# baxandall.net
KiCad netlist of a schematic drawn in EAGLE
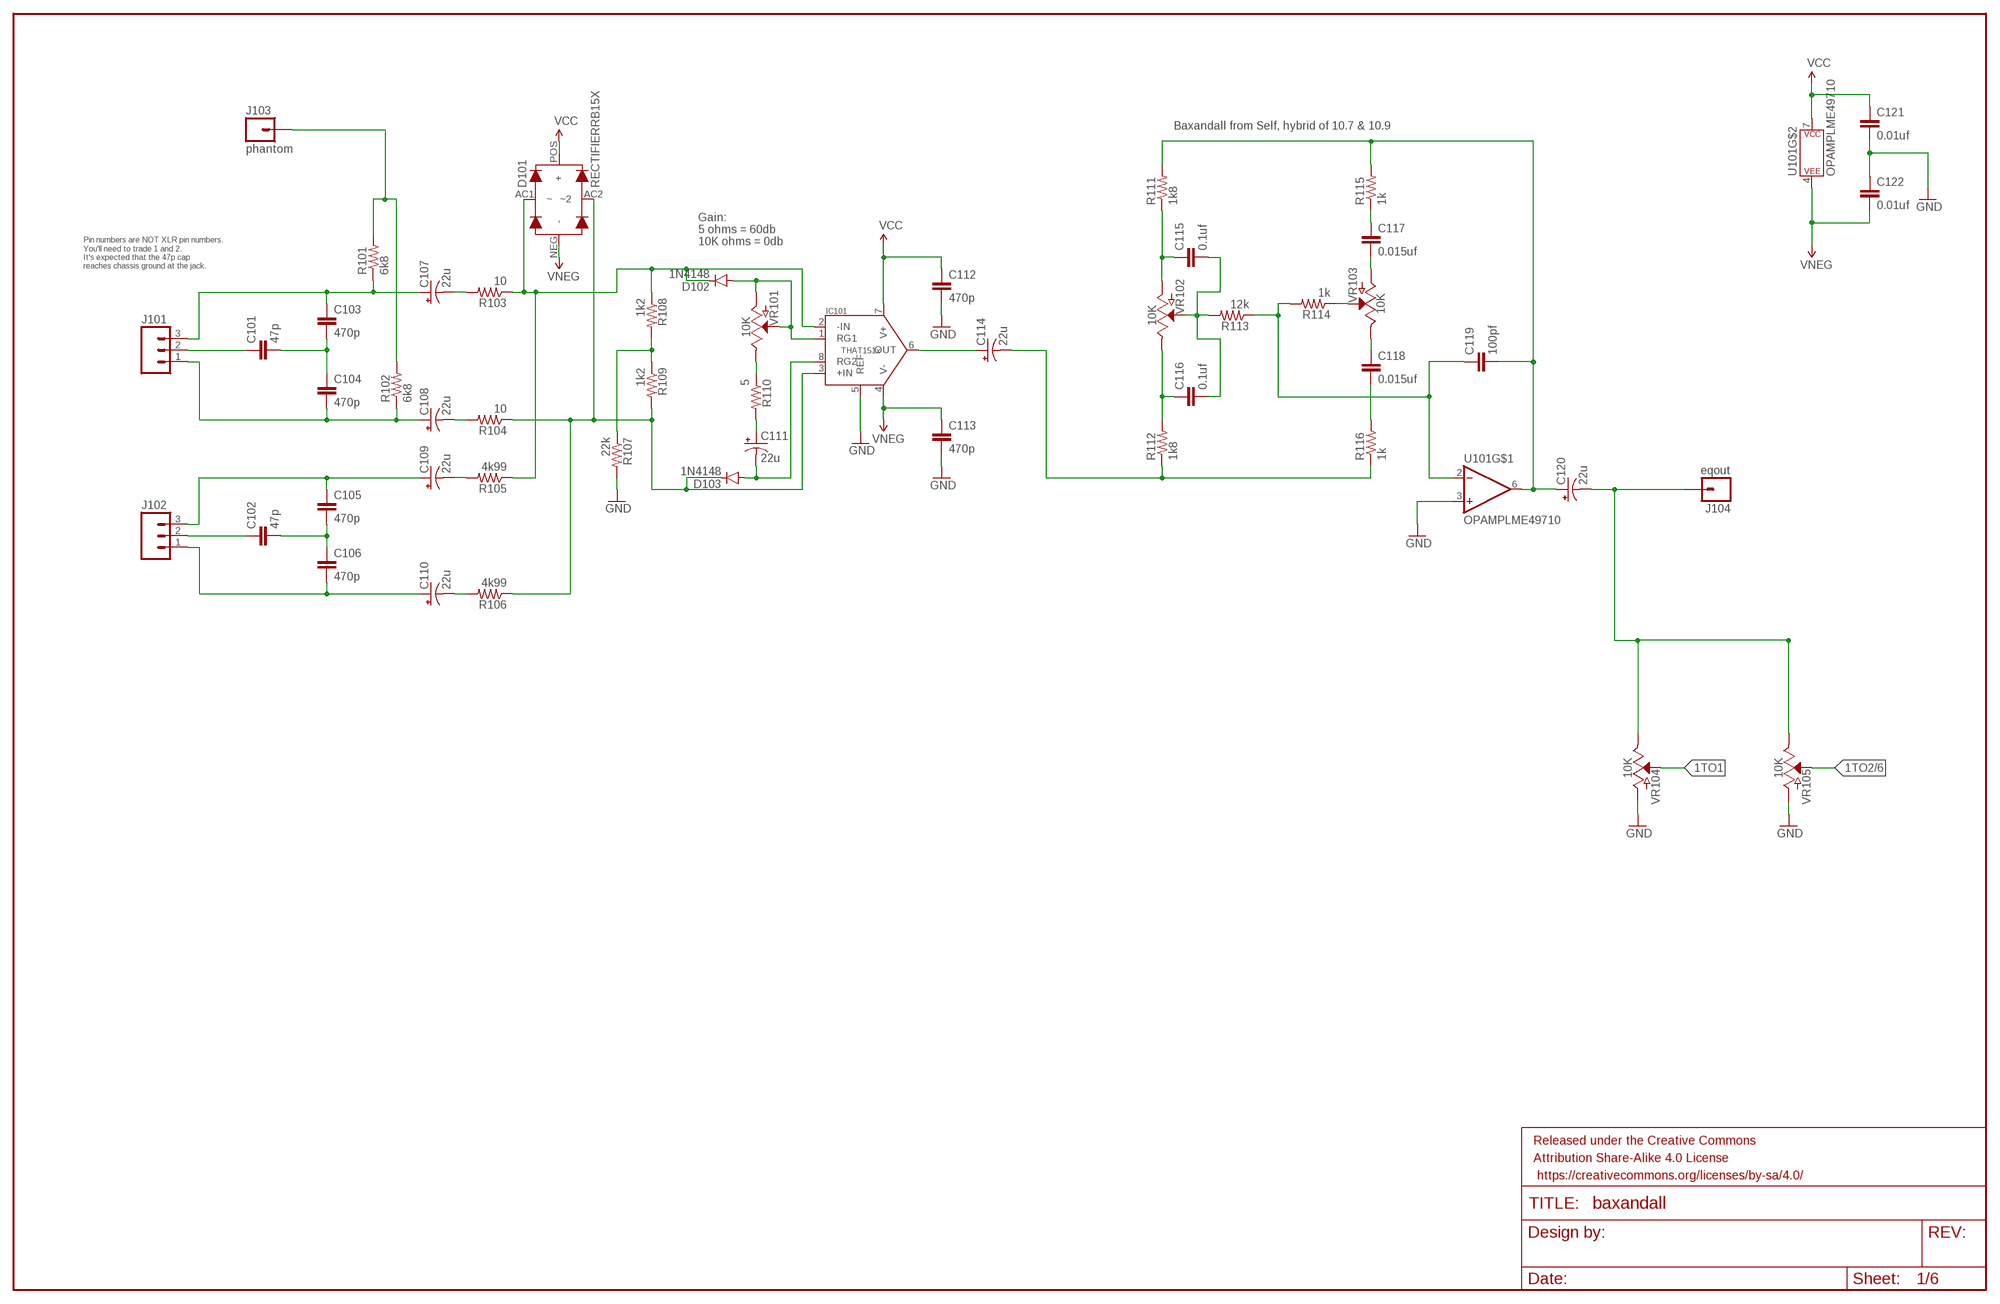
[diagram p0: schematic, sheet 1]
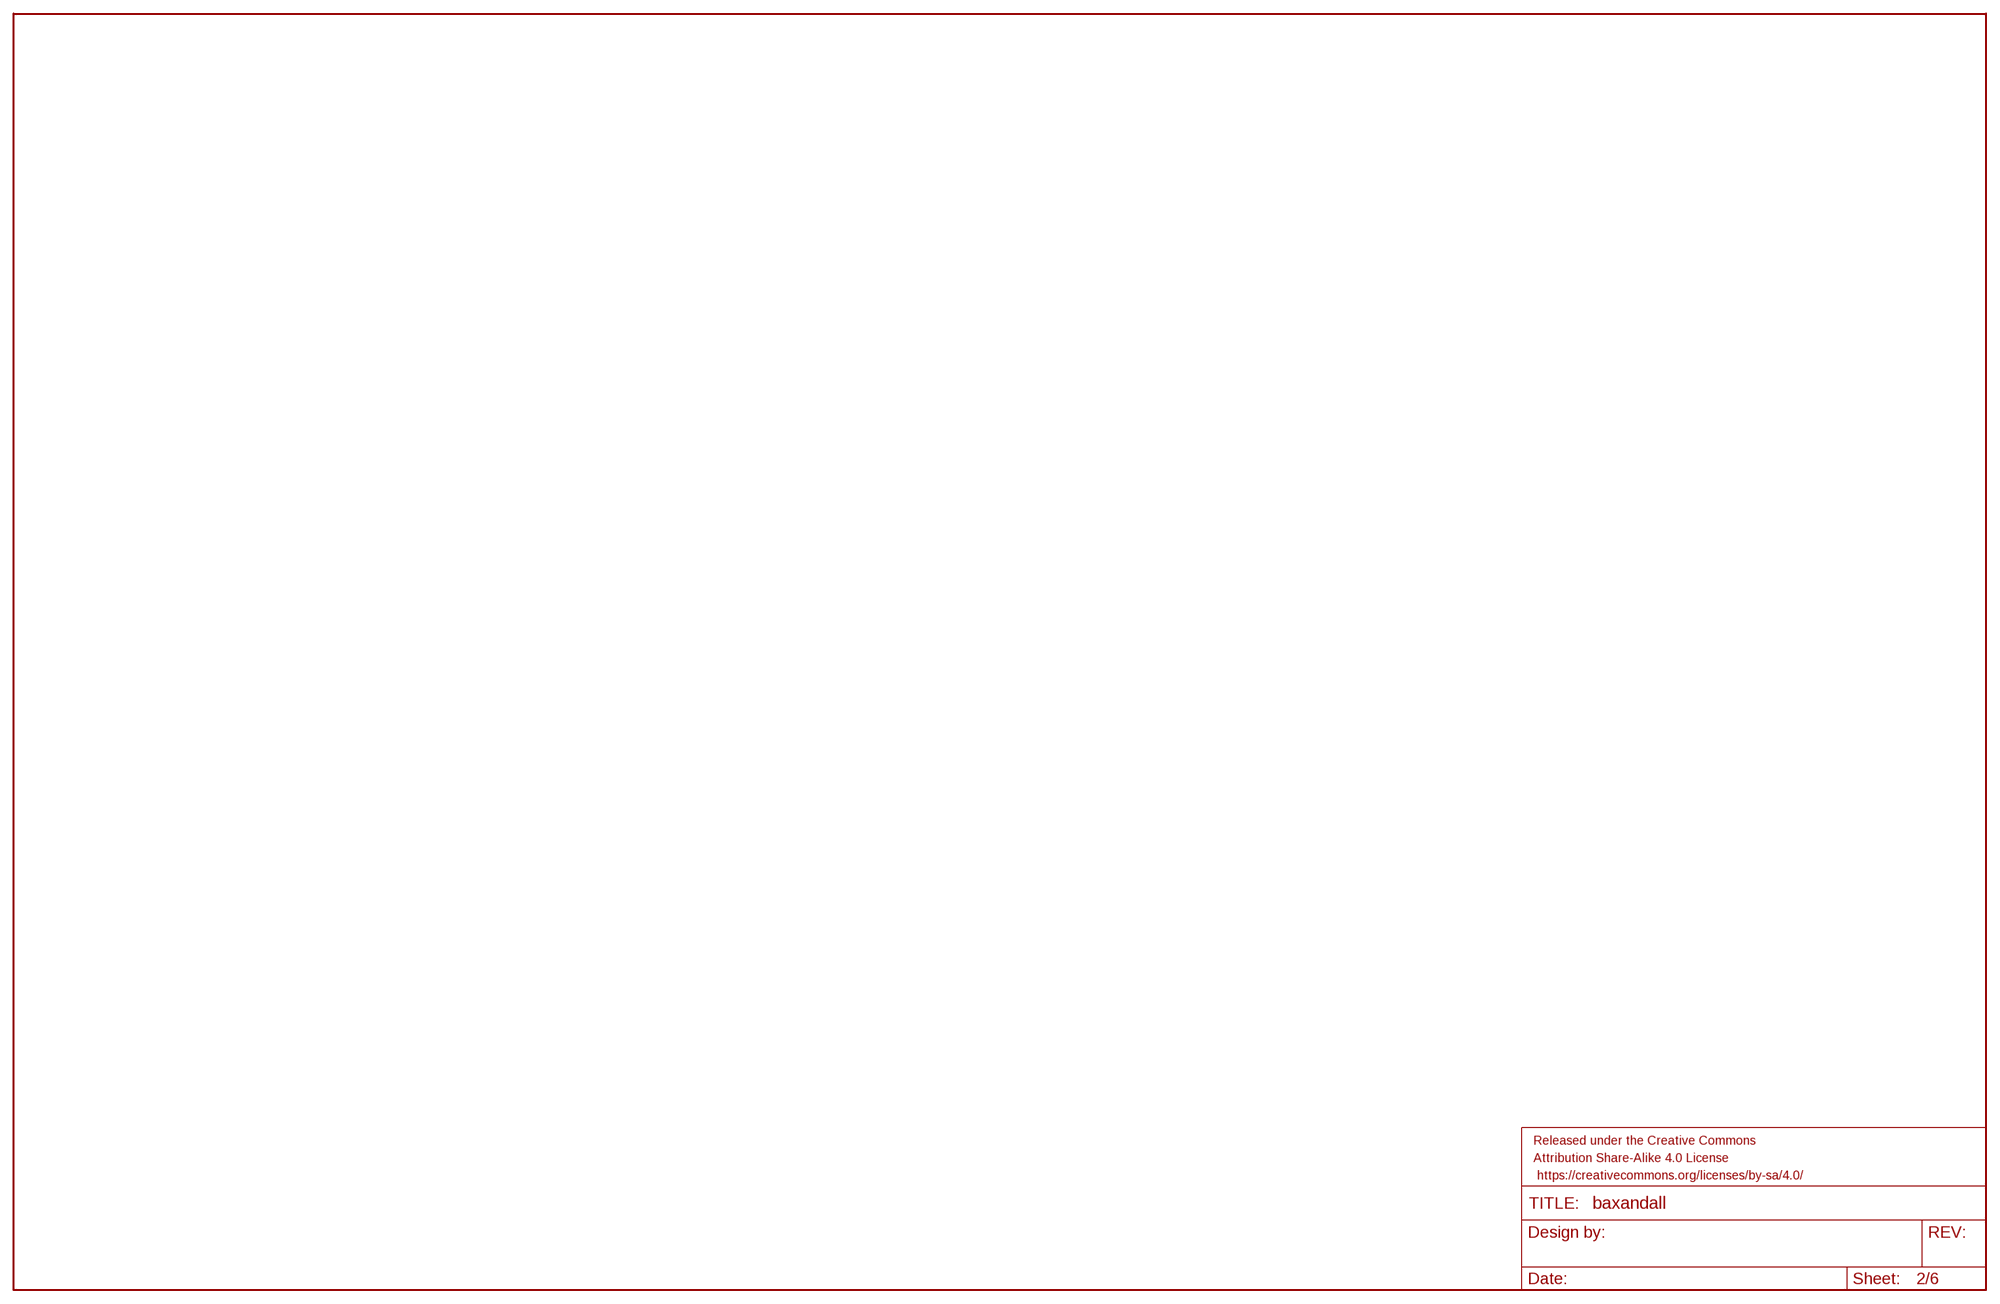
[diagram p1: schematic, sheet 2]
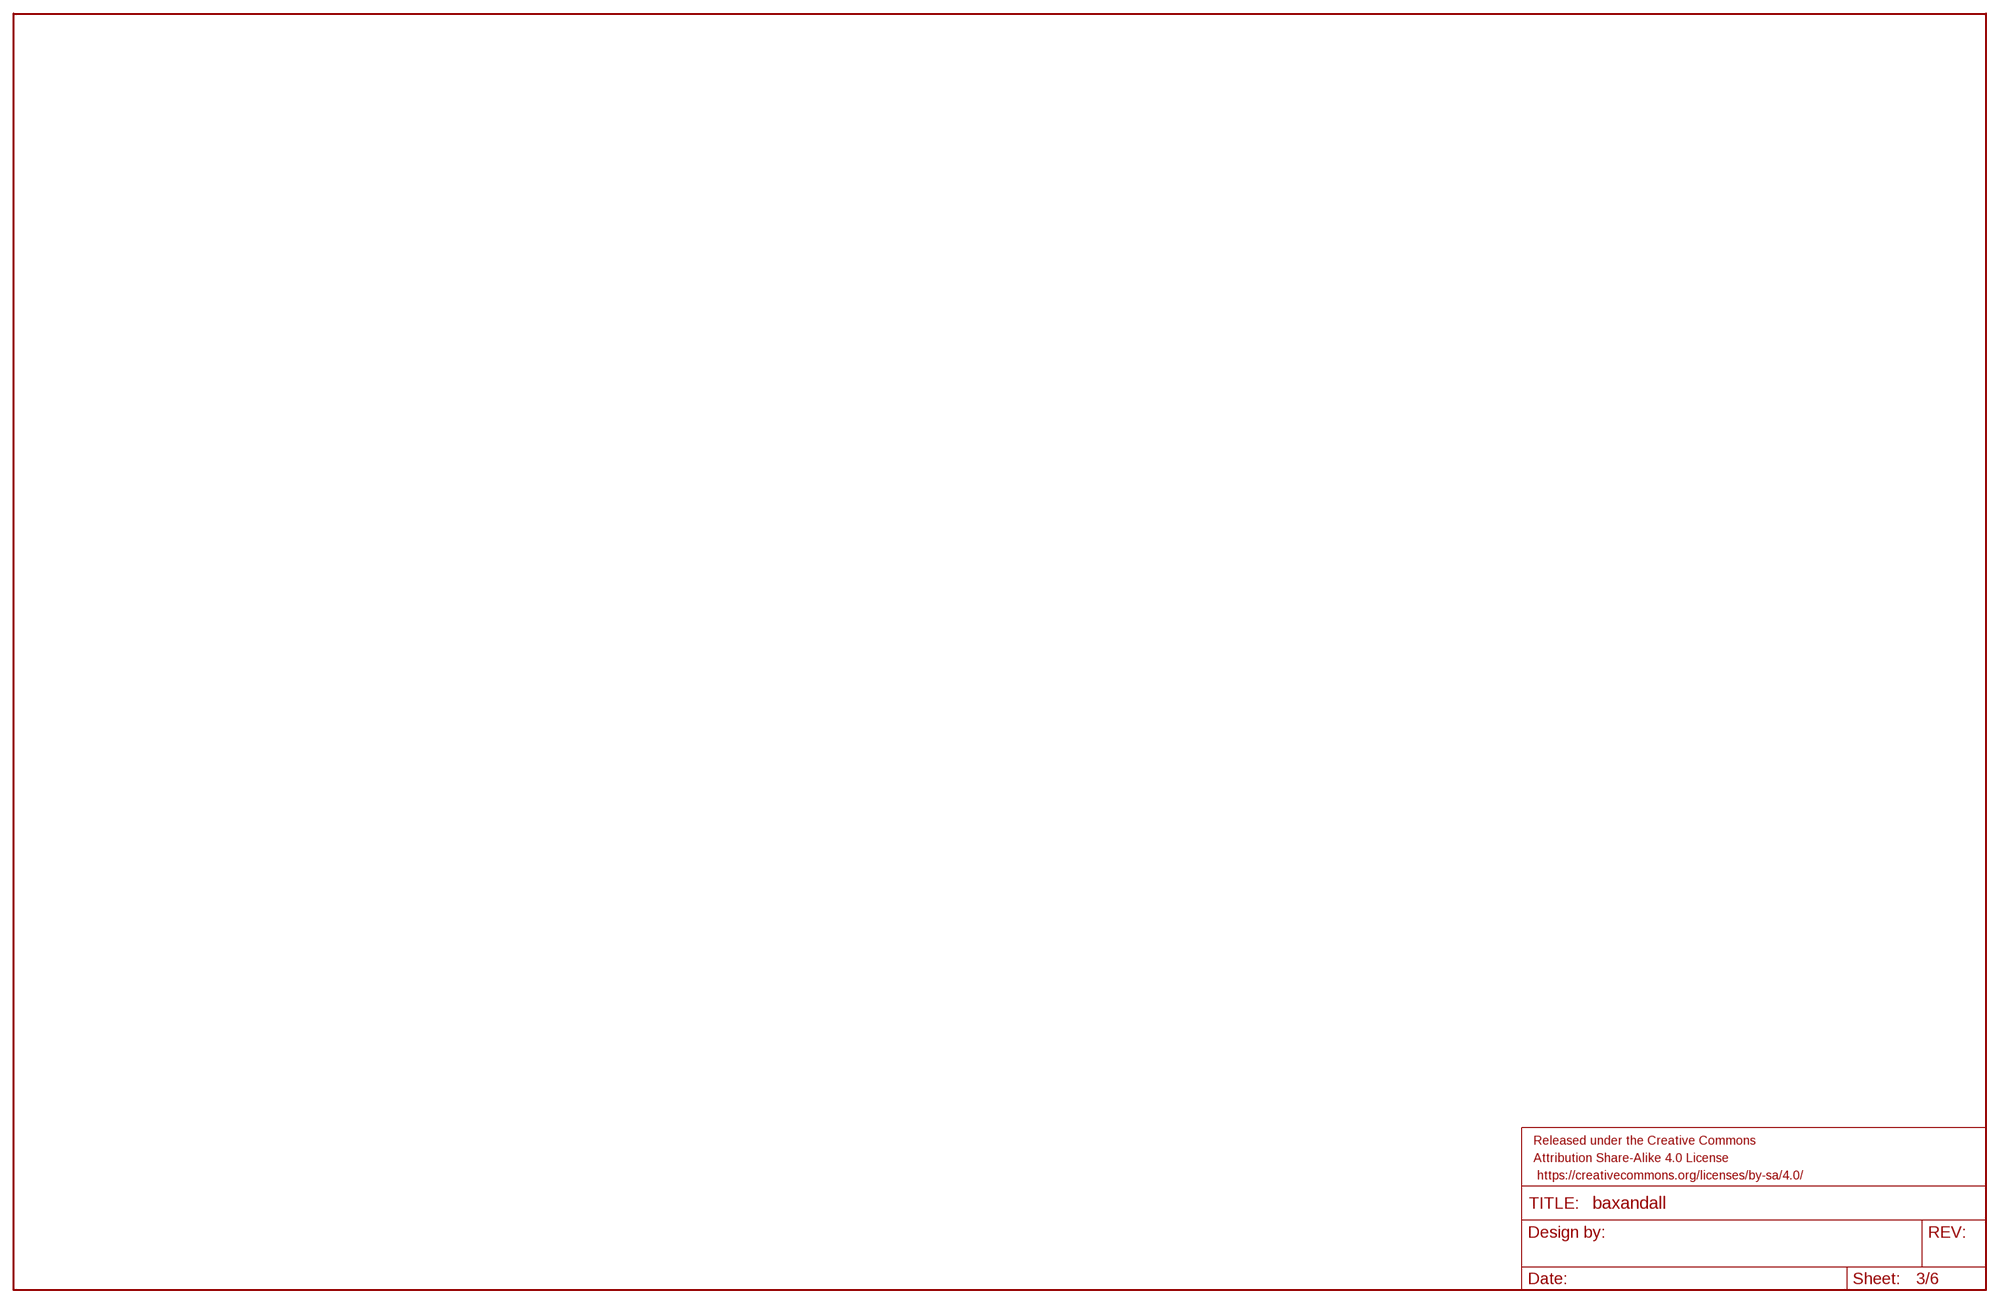
[diagram p2: schematic, sheet 3]
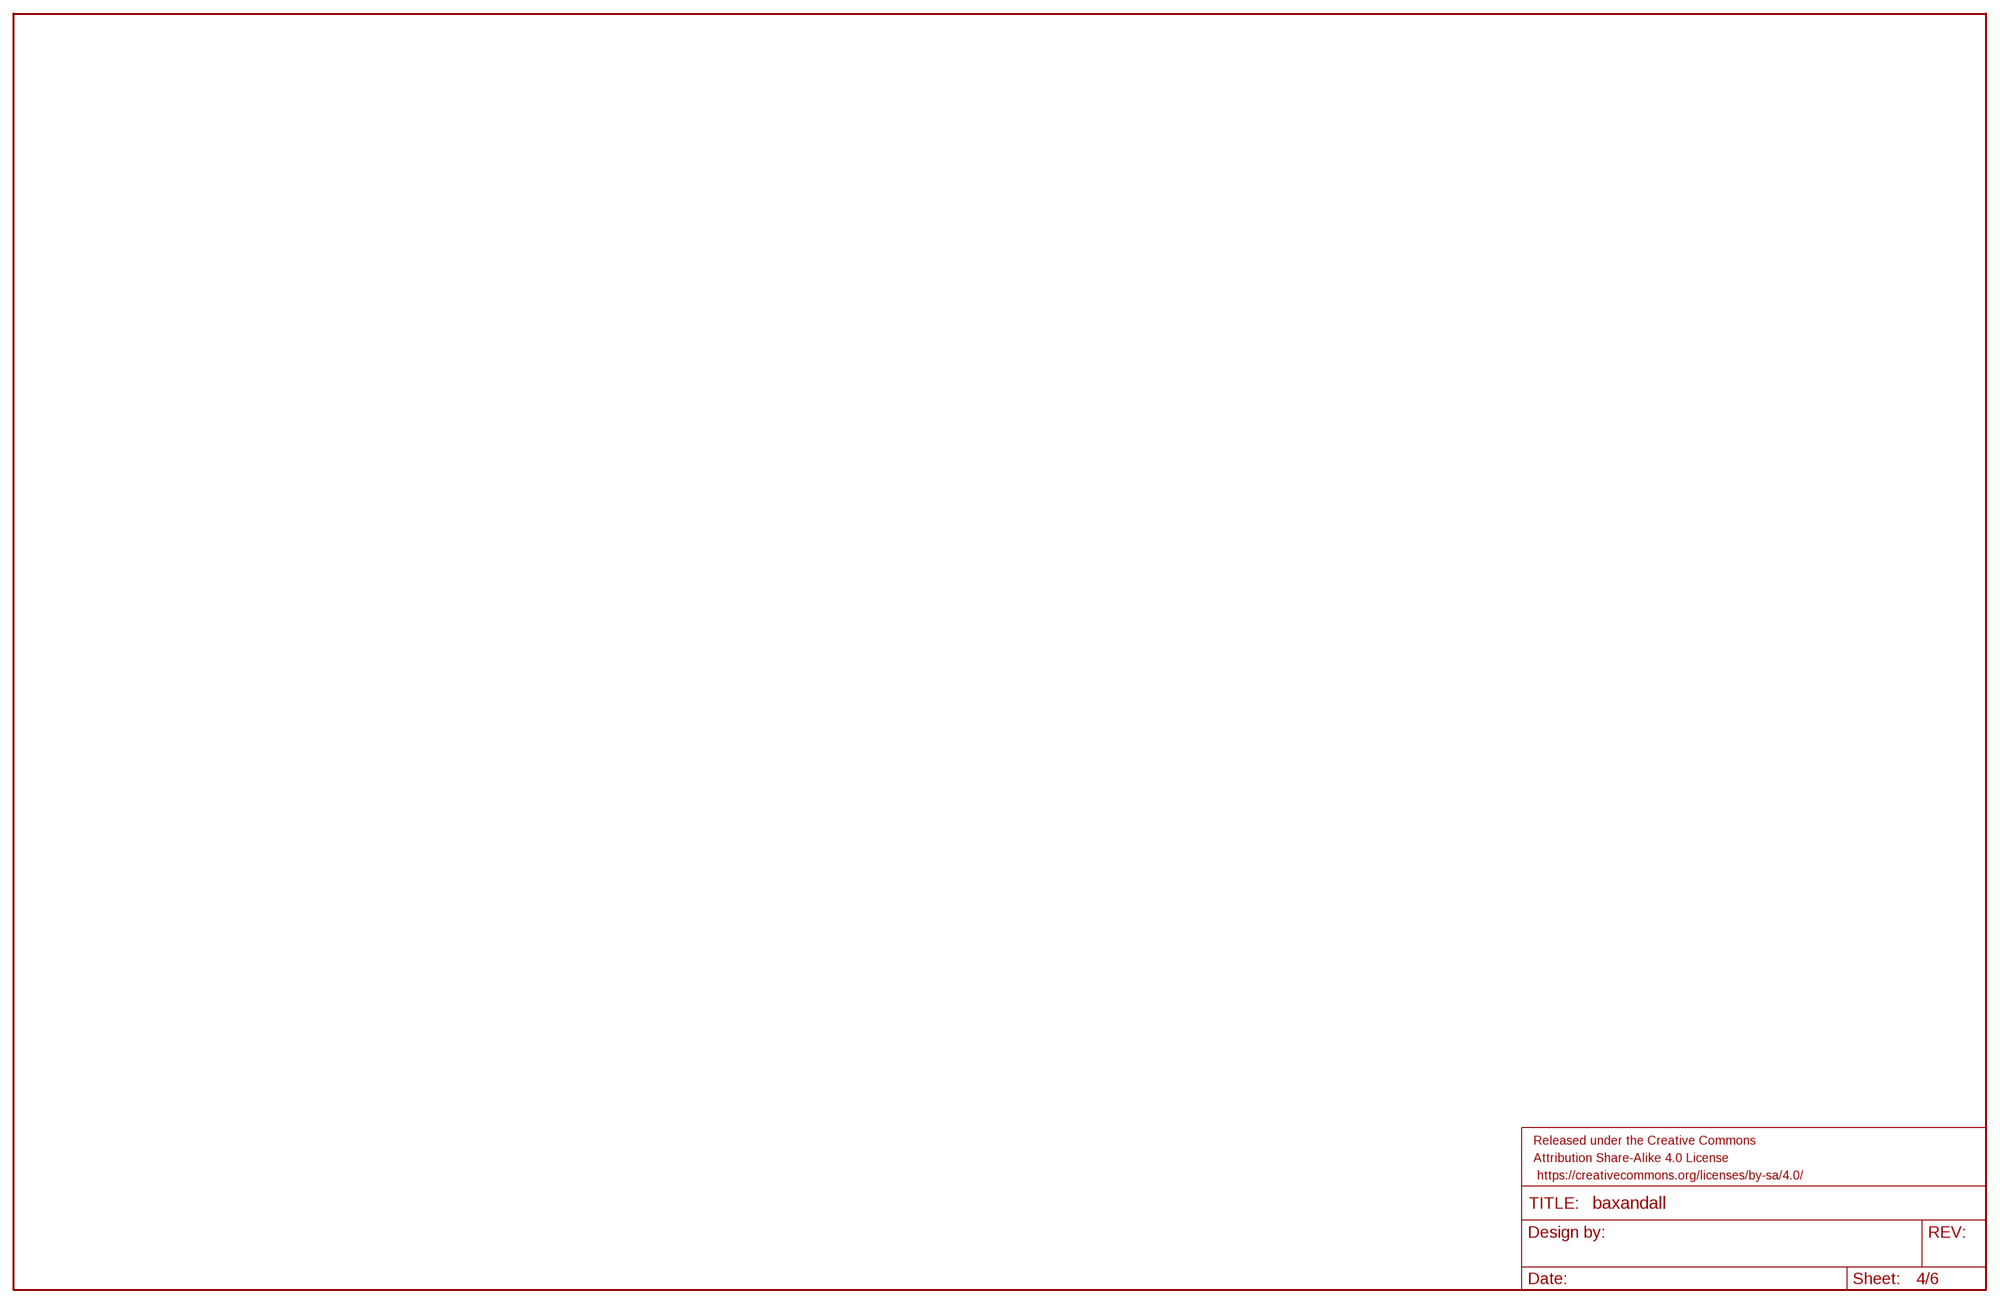
[diagram p3: schematic, sheet 4]
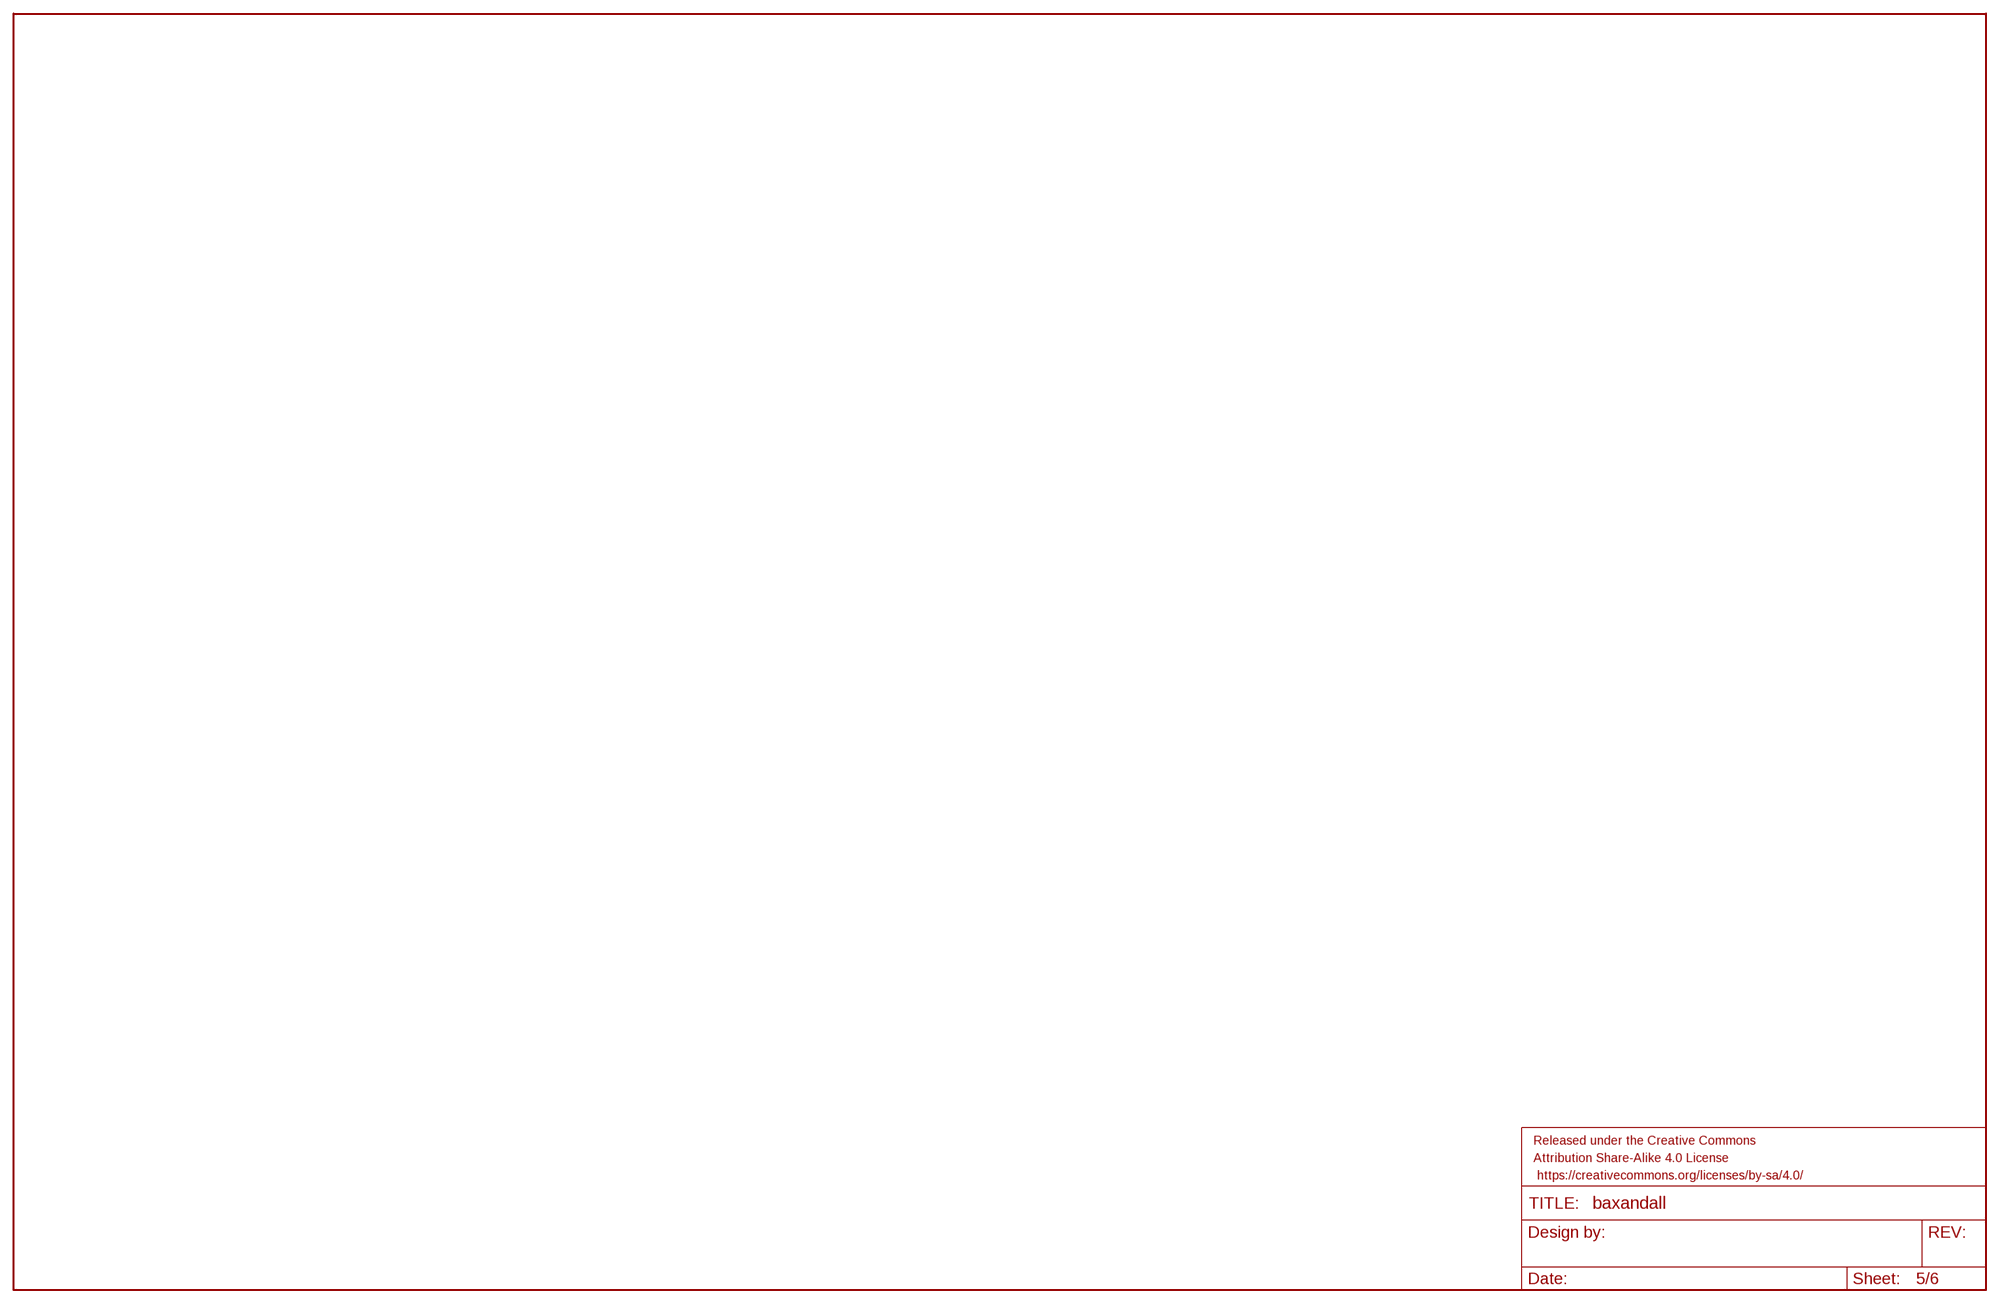
[diagram p4: schematic, sheet 5]
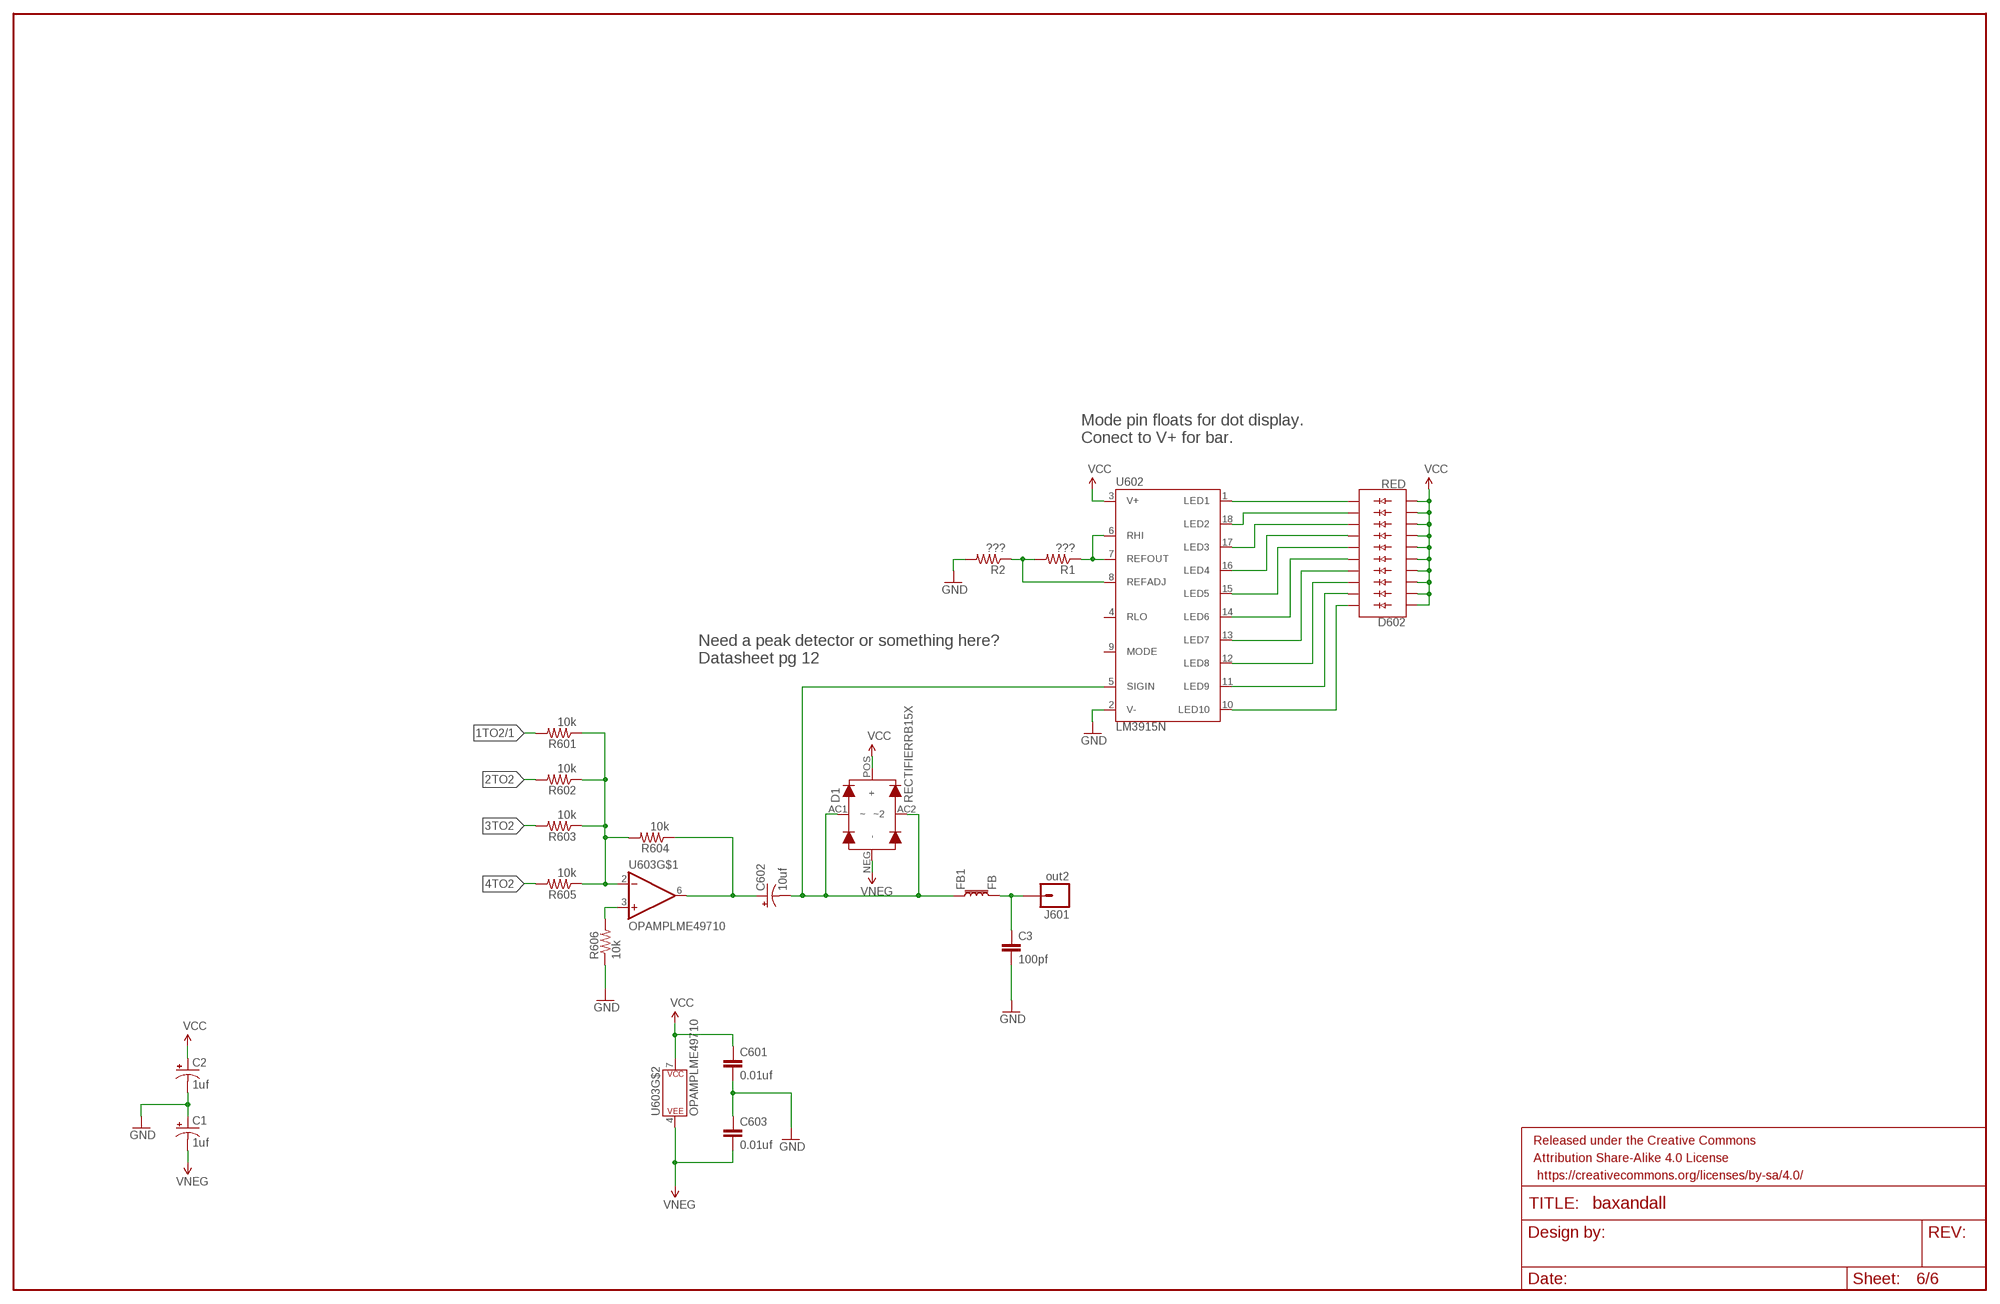
[diagram p5: schematic, sheet 6]

(export (version "E")
  (design (tool "Eeschema 10.0.6"))
  (components
    (comp (ref "FRAME401")
      (value "FRAME-LEDGER")
      (footprint "eagle-import:CREATIVE_COMMONS")
      (libsource (lib "eagle-import") (part "FRAME-LEDGER"))
    )
    (comp (ref "C101")
      (value "47p")
      (footprint "eagle-import:CAP-PTH-SMALL")
      (libsource (lib "eagle-import") (part "CAPPTH"))
    )
    (comp (ref "C102")
      (value "47p")
      (footprint "eagle-import:CAP-PTH-SMALL")
      (libsource (lib "eagle-import") (part "CAPPTH"))
    )
    (comp (ref "C103")
      (value "470p")
      (footprint "eagle-import:CAP-PTH-SMALL")
      (libsource (lib "eagle-import") (part "CAPPTH"))
    )
    (comp (ref "C104")
      (value "470p")
      (footprint "eagle-import:CAP-PTH-SMALL")
      (libsource (lib "eagle-import") (part "CAPPTH"))
    )
    (comp (ref "C105")
      (value "470p")
      (footprint "eagle-import:CAP-PTH-SMALL")
      (libsource (lib "eagle-import") (part "CAPPTH"))
    )
    (comp (ref "C106")
      (value "470p")
      (footprint "eagle-import:CAP-PTH-SMALL")
      (libsource (lib "eagle-import") (part "CAPPTH"))
    )
    (comp (ref "C107")
      (value "22u")
      (footprint "eagle-import:CPOL-RADIAL-100UF-25V")
      (libsource (lib "eagle-import") (part "100UF-25V-20%(PTH)"))
    )
    (comp (ref "C108")
      (value "22u")
      (footprint "eagle-import:CPOL-RADIAL-100UF-25V")
      (libsource (lib "eagle-import") (part "100UF-25V-20%(PTH)"))
    )
    (comp (ref "C109")
      (value "22u")
      (footprint "eagle-import:CPOL-RADIAL-100UF-25V")
      (libsource (lib "eagle-import") (part "100UF-25V-20%(PTH)"))
    )
    (comp (ref "C110")
      (value "22u")
      (footprint "eagle-import:CPOL-RADIAL-100UF-25V")
      (libsource (lib "eagle-import") (part "100UF-25V-20%(PTH)"))
    )
    (comp (ref "C111")
      (value "22u")
      (footprint "eagle-import:CPOL-RADIAL-100UF-25V")
      (libsource (lib "eagle-import") (part "100UF-25V-20%(PTH)"))
    )
    (comp (ref "C112")
      (value "470p")
      (footprint "eagle-import:CAP-PTH-SMALL")
      (libsource (lib "eagle-import") (part "CAPPTH"))
    )
    (comp (ref "C113")
      (value "470p")
      (footprint "eagle-import:CAP-PTH-SMALL")
      (libsource (lib "eagle-import") (part "CAPPTH"))
    )
    (comp (ref "C114")
      (value "22u")
      (footprint "eagle-import:CPOL-RADIAL-100UF-25V")
      (libsource (lib "eagle-import") (part "100UF-25V-20%(PTH)"))
    )
    (comp (ref "C115")
      (value "0.1uf")
      (footprint "eagle-import:WIMA-MKS2-2.5X7.2")
      (libsource (lib "eagle-import") (part "WIMA-MKS20.1UF"))
    )
    (comp (ref "C116")
      (value "0.1uf")
      (footprint "eagle-import:WIMA-MKS2-2.5X7.2")
      (libsource (lib "eagle-import") (part "WIMA-MKS20.1UF"))
    )
    (comp (ref "C117")
      (value "0.015uf")
      (footprint "eagle-import:WIMA-MKS2-2.5X7.2")
      (libsource (lib "eagle-import") (part "WIMA-MKS20.015UF"))
    )
    (comp (ref "C118")
      (value "0.015uf")
      (footprint "eagle-import:WIMA-MKS2-2.5X7.2")
      (libsource (lib "eagle-import") (part "WIMA-MKS20.015UF"))
    )
    (comp (ref "C119")
      (value "100pf")
      (footprint "eagle-import:CAP-PTH-SMALL")
      (libsource (lib "eagle-import") (part "CAPPTH"))
    )
    (comp (ref "C120")
      (value "22u")
      (footprint "eagle-import:CPOL-RADIAL-100UF-25V")
      (libsource (lib "eagle-import") (part "100UF-25V-20%(PTH)"))
    )
    (comp (ref "C121")
      (value "0.01uf")
      (footprint "eagle-import:WIMA-MKS2-2.5X7.2")
      (libsource (lib "eagle-import") (part "WIMA-MKS20.01UF"))
    )
    (comp (ref "C122")
      (value "0.01uf")
      (footprint "eagle-import:WIMA-MKS2-2.5X7.2")
      (libsource (lib "eagle-import") (part "WIMA-MKS20.01UF"))
    )
    (comp (ref "D101")
      (value "RECTIFIERRB15X")
      (footprint "eagle-import:SM-RECTIFIER")
      (libsource (lib "eagle-import") (part "RECTIFIERRB15X"))
    )
    (comp (ref "D102")
      (value "1N4148")
      (footprint "eagle-import:DIODE-1N4148")
      (libsource (lib "eagle-import") (part "DIODE1N4148"))
    )
    (comp (ref "D103")
      (value "1N4148")
      (footprint "eagle-import:DIODE-1N4148")
      (libsource (lib "eagle-import") (part "DIODE1N4148"))
    )
    (comp (ref "FRAME101")
      (value "FRAME-LEDGER")
      (footprint "eagle-import:CREATIVE_COMMONS")
      (libsource (lib "eagle-import") (part "FRAME-LEDGER"))
    )
    (comp (ref "IC101")
      (value "THAT151x")
      (footprint "eagle-import:DIP08-KIT")
      (libsource (lib "eagle-import") (part "THAT151X"))
    )
    (comp (ref "J101")
      (value "M031X03_NO_SILK")
      (footprint "eagle-import:1X03_NO_SILK")
      (libsource (lib "eagle-import") (part "M031X03_NO_SILK"))
    )
    (comp (ref "J102")
      (value "M031X03_NO_SILK")
      (footprint "eagle-import:1X03_NO_SILK")
      (libsource (lib "eagle-import") (part "M031X03_NO_SILK"))
    )
    (comp (ref "J103")
      (value "phantom")
      (footprint "eagle-import:1X01NS-KIT")
      (libsource (lib "eagle-import") (part "M01NOSILK-KIT"))
    )
    (comp (ref "J104")
      (value "eqout")
      (footprint "eagle-import:1X01NS-KIT")
      (libsource (lib "eagle-import") (part "M01NOSILK-KIT"))
    )
    (comp (ref "R101")
      (value "6k8")
      (footprint "eagle-import:AXIAL-0.3")
      (libsource (lib "eagle-import") (part "10KOHM-1/4W-1%(PTH)HORIZ"))
    )
    (comp (ref "R102")
      (value "6k8")
      (footprint "eagle-import:AXIAL-0.3")
      (libsource (lib "eagle-import") (part "10KOHM-1/4W-1%(PTH)HORIZ"))
    )
    (comp (ref "R103")
      (value "10")
      (footprint "eagle-import:AXIAL-0.3")
      (libsource (lib "eagle-import") (part "10KOHM-1/4W-1%(PTH)HORIZ"))
    )
    (comp (ref "R104")
      (value "10")
      (footprint "eagle-import:AXIAL-0.3")
      (libsource (lib "eagle-import") (part "10KOHM-1/4W-1%(PTH)HORIZ"))
    )
    (comp (ref "R105")
      (value "4k99")
      (footprint "eagle-import:AXIAL-0.3")
      (libsource (lib "eagle-import") (part "10KOHM-1/4W-1%(PTH)HORIZ"))
    )
    (comp (ref "R106")
      (value "4k99")
      (footprint "eagle-import:AXIAL-0.3")
      (libsource (lib "eagle-import") (part "10KOHM-1/4W-1%(PTH)HORIZ"))
    )
    (comp (ref "R107")
      (value "22k")
      (footprint "eagle-import:AXIAL-0.3")
      (libsource (lib "eagle-import") (part "10KOHM-1/4W-1%(PTH)HORIZ"))
    )
    (comp (ref "R108")
      (value "1k2")
      (footprint "eagle-import:AXIAL-0.3")
      (libsource (lib "eagle-import") (part "10KOHM-1/4W-1%(PTH)HORIZ"))
    )
    (comp (ref "R109")
      (value "1k2")
      (footprint "eagle-import:AXIAL-0.3")
      (libsource (lib "eagle-import") (part "10KOHM-1/4W-1%(PTH)HORIZ"))
    )
    (comp (ref "R110")
      (value "5")
      (footprint "eagle-import:AXIAL-0.3")
      (libsource (lib "eagle-import") (part "10KOHM-1/4W-1%(PTH)HORIZ"))
    )
    (comp (ref "R111")
      (value "1k8")
      (footprint "eagle-import:AXIAL-0.3")
      (libsource (lib "eagle-import") (part "10KOHM-1/4W-1%(PTH)HORIZ"))
    )
    (comp (ref "R112")
      (value "1k8")
      (footprint "eagle-import:AXIAL-0.3")
      (libsource (lib "eagle-import") (part "10KOHM-1/4W-1%(PTH)HORIZ"))
    )
    (comp (ref "R113")
      (value "12k")
      (footprint "eagle-import:AXIAL-0.3")
      (libsource (lib "eagle-import") (part "10KOHM-1/4W-1%(PTH)HORIZ"))
    )
    (comp (ref "R114")
      (value "1k")
      (footprint "eagle-import:AXIAL-0.3")
      (libsource (lib "eagle-import") (part "10KOHM-1/4W-1%(PTH)HORIZ"))
    )
    (comp (ref "R115")
      (value "1k")
      (footprint "eagle-import:AXIAL-0.3")
      (libsource (lib "eagle-import") (part "10KOHM-1/4W-1%(PTH)HORIZ"))
    )
    (comp (ref "R116")
      (value "1k")
      (footprint "eagle-import:AXIAL-0.3")
      (libsource (lib "eagle-import") (part "10KOHM-1/4W-1%(PTH)HORIZ"))
    )
    (comp (ref "U101")
      (value "OPAMPLME49710")
      (footprint "eagle-import:DIP08-KIT")
      (fields (field (name "MFR") "lme49710"))
      (libsource (lib "eagle-import") (part "OPAMPLME49710"))
    )
    (comp (ref "VR101")
      (value "10K")
      (footprint "eagle-import:ROT-SW-POT")
      (libsource (lib "eagle-import") (part "POTROT-SW-POT"))
    )
    (comp (ref "VR102")
      (value "10K")
      (footprint "eagle-import:ALPHA-RV24AF40-POT")
      (libsource (lib "eagle-import") (part "POT10K-VERTPIN"))
    )
    (comp (ref "VR103")
      (value "10K")
      (footprint "eagle-import:ALPHA-RV24AF40-POT")
      (libsource (lib "eagle-import") (part "POT10K-VERTPIN"))
    )
    (comp (ref "VR104")
      (value "10K")
      (footprint "eagle-import:ALPHA-RV24AF40-POT")
      (libsource (lib "eagle-import") (part "POT10K-VERTPIN"))
    )
    (comp (ref "VR105")
      (value "10K")
      (footprint "eagle-import:ALPHA-RV24AF40-POT")
      (libsource (lib "eagle-import") (part "POT10K-VERTPIN"))
    )
    (comp (ref "FRAME301")
      (value "FRAME-LEDGER")
      (footprint "eagle-import:CREATIVE_COMMONS")
      (libsource (lib "eagle-import") (part "FRAME-LEDGER"))
    )
    (comp (ref "FRAME201")
      (value "FRAME-LEDGER")
      (footprint "eagle-import:CREATIVE_COMMONS")
      (libsource (lib "eagle-import") (part "FRAME-LEDGER"))
    )
    (comp (ref "FRAME501")
      (value "FRAME-LEDGER")
      (footprint "eagle-import:CREATIVE_COMMONS")
      (libsource (lib "eagle-import") (part "FRAME-LEDGER"))
    )
    (comp (ref "C1")
      (value "1uf")
      (footprint "eagle-import:CPOL-RADIAL-10UF-25V")
      (libsource (lib "eagle-import") (part "CAP_POLPTH2"))
    )
    (comp (ref "C2")
      (value "1uf")
      (footprint "eagle-import:CPOL-RADIAL-10UF-25V")
      (libsource (lib "eagle-import") (part "CAP_POLPTH2"))
    )
    (comp (ref "C3")
      (value "100pf")
      (footprint "eagle-import:CAP-PTH-SMALL")
      (libsource (lib "eagle-import") (part "CAPPTH"))
    )
    (comp (ref "C601")
      (value "0.01uf")
      (footprint "eagle-import:WIMA-MKS2-2.5X7.2")
      (libsource (lib "eagle-import") (part "WIMA-MKS20.01UF"))
    )
    (comp (ref "C602")
      (value "10uf")
      (footprint "eagle-import:CPOL-RADIAL-10UF-25V")
      (libsource (lib "eagle-import") (part "10UF-25V-20%(PTH)"))
    )
    (comp (ref "C603")
      (value "0.01uf")
      (footprint "eagle-import:WIMA-MKS2-2.5X7.2")
      (libsource (lib "eagle-import") (part "WIMA-MKS20.01UF"))
    )
    (comp (ref "D1")
      (value "RECTIFIERRB15X")
      (footprint "eagle-import:SM-RECTIFIER")
      (libsource (lib "eagle-import") (part "RECTIFIERRB15X"))
    )
    (comp (ref "D602")
      (value "RED")
      (footprint "eagle-import:LED_BARGRAPH_10")
      (libsource (lib "eagle-import") (part "LED_BARGRAPH_10RED"))
    )
    (comp (ref "FB1")
      (value "FB")
      (footprint "eagle-import:BEAD")
      (libsource (lib "eagle-import") (part "FB"))
    )
    (comp (ref "FRAME601")
      (value "FRAME-LEDGER")
      (footprint "eagle-import:CREATIVE_COMMONS")
      (libsource (lib "eagle-import") (part "FRAME-LEDGER"))
    )
    (comp (ref "J601")
      (value "out2")
      (footprint "eagle-import:1X01NS-KIT")
      (libsource (lib "eagle-import") (part "M01NOSILK-KIT"))
    )
    (comp (ref "R1")
      (value "???")
      (footprint "eagle-import:AXIAL-0.3")
      (libsource (lib "eagle-import") (part "RESISTORAXIAL-0.3"))
    )
    (comp (ref "R2")
      (value "???")
      (footprint "eagle-import:AXIAL-0.3")
      (libsource (lib "eagle-import") (part "RESISTORAXIAL-0.3"))
    )
    (comp (ref "R601")
      (value "10k")
      (footprint "eagle-import:AXIAL-0.3")
      (libsource (lib "eagle-import") (part "RESISTORAXIAL-0.3"))
    )
    (comp (ref "R602")
      (value "10k")
      (footprint "eagle-import:AXIAL-0.3")
      (libsource (lib "eagle-import") (part "RESISTORAXIAL-0.3"))
    )
    (comp (ref "R603")
      (value "10k")
      (footprint "eagle-import:AXIAL-0.3")
      (libsource (lib "eagle-import") (part "RESISTORAXIAL-0.3"))
    )
    (comp (ref "R604")
      (value "10k")
      (footprint "eagle-import:AXIAL-0.3")
      (libsource (lib "eagle-import") (part "RESISTORAXIAL-0.3"))
    )
    (comp (ref "R605")
      (value "10k")
      (footprint "eagle-import:AXIAL-0.3")
      (libsource (lib "eagle-import") (part "RESISTORAXIAL-0.3"))
    )
    (comp (ref "R606")
      (value "10k")
      (footprint "eagle-import:AXIAL-0.3")
      (libsource (lib "eagle-import") (part "RESISTORAXIAL-0.3"))
    )
    (comp (ref "U602")
      (value "LM3915N")
      (footprint "eagle-import:DIL18")
      (libsource (lib "eagle-import") (part "LM391N5"))
    )
    (comp (ref "U603")
      (value "OPAMPLME49710")
      (footprint "eagle-import:DIP08-KIT")
      (fields (field (name "MFR") "lme49710"))
      (libsource (lib "eagle-import") (part "OPAMPLME49710"))
    )
  )
  (nets
    (net (code "1") (name "1TO1") (class "Default")
      (node (ref "VR104") (pin "WIP") (pinfunction "S_WIP") (pintype "passive"))
    )
    (net (code "2") (name "1TO2") (class "Default")
      (node (ref "R601") (pin "P$2") (pinfunction "2_P$2") (pintype "passive"))
      (node (ref "VR105") (pin "WIP") (pinfunction "S_WIP") (pintype "passive"))
    )
    (net (code "3") (name "2TO2") (class "Default")
      (node (ref "R602") (pin "P$2") (pinfunction "2_P$2") (pintype "passive"))
    )
    (net (code "4") (name "3TO2") (class "Default")
      (node (ref "R603") (pin "P$2") (pinfunction "2_P$2") (pintype "passive"))
    )
    (net (code "5") (name "4TO2") (class "Default")
      (node (ref "R605") (pin "P$2") (pinfunction "2_P$2") (pintype "passive"))
    )
    (net (code "6") (name "GND") (class "Default")
      (node (ref "C1") (pin "1") (pinfunction "+_1") (pintype "passive"))
      (node (ref "C112") (pin "2") (pinfunction "2_2") (pintype "passive"))
      (node (ref "C113") (pin "2") (pinfunction "2_2") (pintype "passive"))
      (node (ref "C121") (pin "P$2") (pinfunction "2_P$2") (pintype "passive"))
      (node (ref "C122") (pin "P$1") (pinfunction "1_P$1") (pintype "passive"))
      (node (ref "C2") (pin "2") (pinfunction "-_2") (pintype "passive"))
      (node (ref "C3") (pin "2") (pinfunction "2_2") (pintype "passive"))
      (node (ref "C601") (pin "P$2") (pinfunction "2_P$2") (pintype "passive"))
      (node (ref "C603") (pin "P$1") (pinfunction "1_P$1") (pintype "passive"))
      (node (ref "IC101") (pin "5") (pinfunction "REF_5") (pintype "bidirectional"))
      (node (ref "R107") (pin "P$2") (pinfunction "2_P$2") (pintype "passive"))
      (node (ref "R2") (pin "P$2") (pinfunction "2_P$2") (pintype "passive"))
      (node (ref "R606") (pin "P$1") (pinfunction "1_P$1") (pintype "passive"))
      (node (ref "U101") (pin "3") (pinfunction "+IN_3") (pintype "input"))
      (node (ref "U602") (pin "2") (pinfunction "V-_2") (pintype "power_in"))
      (node (ref "VR104") (pin "CCW") (pinfunction "A_CCW") (pintype "passive"))
      (node (ref "VR105") (pin "CCW") (pinfunction "A_CCW") (pintype "passive"))
    )
    (net (code "7") (name "Net-(C101-Pad1)") (class "Default")
      (node (ref "C101") (pin "1") (pinfunction "1_1") (pintype "passive"))
      (node (ref "J101") (pin "2") (pinfunction "2_2") (pintype "passive"))
    )
    (net (code "8") (name "Net-(C101-Pad2)") (class "Default")
      (node (ref "C101") (pin "2") (pinfunction "2_2") (pintype "passive"))
      (node (ref "C103") (pin "2") (pinfunction "2_2") (pintype "passive"))
      (node (ref "C104") (pin "1") (pinfunction "1_1") (pintype "passive"))
    )
    (net (code "9") (name "Net-(C102-Pad1)") (class "Default")
      (node (ref "C102") (pin "1") (pinfunction "1_1") (pintype "passive"))
      (node (ref "J102") (pin "2") (pinfunction "2_2") (pintype "passive"))
    )
    (net (code "10") (name "Net-(C102-Pad2)") (class "Default")
      (node (ref "C102") (pin "2") (pinfunction "2_2") (pintype "passive"))
      (node (ref "C105") (pin "2") (pinfunction "2_2") (pintype "passive"))
      (node (ref "C106") (pin "1") (pinfunction "1_1") (pintype "passive"))
    )
    (net (code "11") (name "Net-(C107-+)") (class "Default")
      (node (ref "C103") (pin "1") (pinfunction "1_1") (pintype "passive"))
      (node (ref "C107") (pin "1") (pinfunction "+_1") (pintype "passive"))
      (node (ref "J101") (pin "3") (pinfunction "3_3") (pintype "passive"))
      (node (ref "R101") (pin "P$1") (pinfunction "1_P$1") (pintype "passive"))
    )
    (net (code "12") (name "Net-(C107--)") (class "Default")
      (node (ref "C107") (pin "2") (pinfunction "-_2") (pintype "passive"))
      (node (ref "R103") (pin "P$2") (pinfunction "2_P$2") (pintype "passive"))
    )
    (net (code "13") (name "Net-(C108-+)") (class "Default")
      (node (ref "C104") (pin "2") (pinfunction "2_2") (pintype "passive"))
      (node (ref "C108") (pin "1") (pinfunction "+_1") (pintype "passive"))
      (node (ref "J101") (pin "1") (pinfunction "1_1") (pintype "passive"))
      (node (ref "R102") (pin "P$1") (pinfunction "1_P$1") (pintype "passive"))
    )
    (net (code "14") (name "Net-(C108--)") (class "Default")
      (node (ref "C108") (pin "2") (pinfunction "-_2") (pintype "passive"))
      (node (ref "R104") (pin "P$2") (pinfunction "2_P$2") (pintype "passive"))
    )
    (net (code "15") (name "Net-(C109-+)") (class "Default")
      (node (ref "C105") (pin "1") (pinfunction "1_1") (pintype "passive"))
      (node (ref "C109") (pin "1") (pinfunction "+_1") (pintype "passive"))
      (node (ref "J102") (pin "3") (pinfunction "3_3") (pintype "passive"))
    )
    (net (code "16") (name "Net-(C109--)") (class "Default")
      (node (ref "C109") (pin "2") (pinfunction "-_2") (pintype "passive"))
      (node (ref "R105") (pin "P$2") (pinfunction "2_P$2") (pintype "passive"))
    )
    (net (code "17") (name "Net-(C110-+)") (class "Default")
      (node (ref "C106") (pin "2") (pinfunction "2_2") (pintype "passive"))
      (node (ref "C110") (pin "1") (pinfunction "+_1") (pintype "passive"))
      (node (ref "J102") (pin "1") (pinfunction "1_1") (pintype "passive"))
    )
    (net (code "18") (name "Net-(C110--)") (class "Default")
      (node (ref "C110") (pin "2") (pinfunction "-_2") (pintype "passive"))
      (node (ref "R106") (pin "P$2") (pinfunction "2_P$2") (pintype "passive"))
    )
    (net (code "19") (name "Net-(C111-+)") (class "Default")
      (node (ref "C111") (pin "1") (pinfunction "+_1") (pintype "passive"))
      (node (ref "R110") (pin "P$2") (pinfunction "2_P$2") (pintype "passive"))
    )
    (net (code "20") (name "Net-(C111--)") (class "Default")
      (node (ref "C111") (pin "2") (pinfunction "-_2") (pintype "passive"))
      (node (ref "D103") (pin "A") (pinfunction "A_A") (pintype "passive"))
      (node (ref "IC101") (pin "8") (pinfunction "RG2_8") (pintype "bidirectional"))
    )
    (net (code "21") (name "Net-(C114-+)") (class "Default")
      (node (ref "C114") (pin "1") (pinfunction "+_1") (pintype "passive"))
      (node (ref "IC101") (pin "6") (pinfunction "OUT_6") (pintype "bidirectional"))
    )
    (net (code "22") (name "Net-(C114--)") (class "Default")
      (node (ref "C114") (pin "2") (pinfunction "-_2") (pintype "passive"))
      (node (ref "R112") (pin "P$1") (pinfunction "1_P$1") (pintype "passive"))
      (node (ref "R116") (pin "P$1") (pinfunction "1_P$1") (pintype "passive"))
    )
    (net (code "23") (name "Net-(C115-1)") (class "Default")
      (node (ref "C115") (pin "P$1") (pinfunction "1_P$1") (pintype "passive"))
      (node (ref "R111") (pin "P$1") (pinfunction "1_P$1") (pintype "passive"))
      (node (ref "VR102") (pin "CCW") (pinfunction "A_CCW") (pintype "passive"))
    )
    (net (code "24") (name "Net-(C115-2)") (class "Default")
      (node (ref "C115") (pin "P$2") (pinfunction "2_P$2") (pintype "passive"))
      (node (ref "C116") (pin "P$2") (pinfunction "2_P$2") (pintype "passive"))
      (node (ref "R113") (pin "P$2") (pinfunction "2_P$2") (pintype "passive"))
      (node (ref "VR102") (pin "WIP") (pinfunction "S_WIP") (pintype "passive"))
    )
    (net (code "25") (name "Net-(C116-1)") (class "Default")
      (node (ref "C116") (pin "P$1") (pinfunction "1_P$1") (pintype "passive"))
      (node (ref "R112") (pin "P$2") (pinfunction "2_P$2") (pintype "passive"))
      (node (ref "VR102") (pin "CW") (pinfunction "E_CW") (pintype "passive"))
    )
    (net (code "26") (name "Net-(C117-1)") (class "Default")
      (node (ref "C117") (pin "P$1") (pinfunction "1_P$1") (pintype "passive"))
      (node (ref "R115") (pin "P$1") (pinfunction "1_P$1") (pintype "passive"))
    )
    (net (code "27") (name "Net-(C117-2)") (class "Default")
      (node (ref "C117") (pin "P$2") (pinfunction "2_P$2") (pintype "passive"))
      (node (ref "VR103") (pin "CCW") (pinfunction "A_CCW") (pintype "passive"))
    )
    (net (code "28") (name "Net-(C118-1)") (class "Default")
      (node (ref "C118") (pin "P$1") (pinfunction "1_P$1") (pintype "passive"))
      (node (ref "VR103") (pin "CW") (pinfunction "E_CW") (pintype "passive"))
    )
    (net (code "29") (name "Net-(C118-2)") (class "Default")
      (node (ref "C118") (pin "P$2") (pinfunction "2_P$2") (pintype "passive"))
      (node (ref "R116") (pin "P$2") (pinfunction "2_P$2") (pintype "passive"))
    )
    (net (code "30") (name "Net-(C120-+)") (class "Default")
      (node (ref "C119") (pin "2") (pinfunction "2_2") (pintype "passive"))
      (node (ref "C120") (pin "1") (pinfunction "+_1") (pintype "passive"))
      (node (ref "R111") (pin "P$2") (pinfunction "2_P$2") (pintype "passive"))
      (node (ref "R115") (pin "P$2") (pinfunction "2_P$2") (pintype "passive"))
      (node (ref "U101") (pin "6") (pinfunction "OUT_6") (pintype "output"))
    )
    (net (code "31") (name "Net-(C120--)") (class "Default")
      (node (ref "C120") (pin "2") (pinfunction "-_2") (pintype "passive"))
      (node (ref "J104") (pin "1") (pinfunction "1_1") (pintype "passive"))
      (node (ref "VR104") (pin "CW") (pinfunction "E_CW") (pintype "passive"))
      (node (ref "VR105") (pin "CW") (pinfunction "E_CW") (pintype "passive"))
    )
    (net (code "32") (name "Net-(C602-+)") (class "Default")
      (node (ref "C602") (pin "1") (pinfunction "+_1") (pintype "passive"))
      (node (ref "R604") (pin "P$1") (pinfunction "1_P$1") (pintype "passive"))
      (node (ref "U603") (pin "6") (pinfunction "OUT_6") (pintype "output"))
    )
    (net (code "33") (name "Net-(C602--)") (class "Default")
      (node (ref "C602") (pin "2") (pinfunction "-_2") (pintype "passive"))
      (node (ref "D1") (pin "AC1") (pinfunction "~_AC1") (pintype "bidirectional"))
      (node (ref "D1") (pin "AC2") (pinfunction "~{2}_AC2") (pintype "bidirectional"))
      (node (ref "FB1") (pin "P$1") (pinfunction "1_P$1") (pintype "passive"))
      (node (ref "U602") (pin "5") (pinfunction "SIGIN_5") (pintype "input"))
    )
    (net (code "34") (name "Net-(D101-~)") (class "Default")
      (node (ref "D101") (pin "AC1") (pinfunction "~_AC1") (pintype "bidirectional"))
      (node (ref "D102") (pin "C") (pinfunction "C_C") (pintype "passive"))
      (node (ref "IC101") (pin "2") (pinfunction "-IN_2") (pintype "bidirectional"))
      (node (ref "R103") (pin "P$1") (pinfunction "1_P$1") (pintype "passive"))
      (node (ref "R105") (pin "P$1") (pinfunction "1_P$1") (pintype "passive"))
      (node (ref "R108") (pin "P$1") (pinfunction "1_P$1") (pintype "passive"))
    )
    (net (code "35") (name "Net-(D101-~{2})") (class "Default")
      (node (ref "D101") (pin "AC2") (pinfunction "~{2}_AC2") (pintype "bidirectional"))
      (node (ref "D103") (pin "C") (pinfunction "C_C") (pintype "passive"))
      (node (ref "IC101") (pin "3") (pinfunction "+IN_3") (pintype "bidirectional"))
      (node (ref "R104") (pin "P$1") (pinfunction "1_P$1") (pintype "passive"))
      (node (ref "R106") (pin "P$1") (pinfunction "1_P$1") (pintype "passive"))
      (node (ref "R109") (pin "P$2") (pinfunction "2_P$2") (pintype "passive"))
    )
    (net (code "36") (name "Net-(D602-C)") (class "Default")
      (node (ref "D602") (pin "20") (pinfunction "C_20") (pintype "passive"))
      (node (ref "U602") (pin "10") (pinfunction "LED10_10") (pintype "output"))
    )
    (net (code "37") (name "Net-(D602-C1)") (class "Default")
      (node (ref "D602") (pin "19") (pinfunction "C1_19") (pintype "passive"))
      (node (ref "U602") (pin "11") (pinfunction "LED9_11") (pintype "output"))
    )
    (net (code "38") (name "Net-(D602-C2)") (class "Default")
      (node (ref "D602") (pin "18") (pinfunction "C2_18") (pintype "passive"))
      (node (ref "U602") (pin "12") (pinfunction "LED8_12") (pintype "output"))
    )
    (net (code "39") (name "Net-(D602-C3)") (class "Default")
      (node (ref "D602") (pin "17") (pinfunction "C3_17") (pintype "passive"))
      (node (ref "U602") (pin "13") (pinfunction "LED7_13") (pintype "output"))
    )
    (net (code "40") (name "Net-(D602-C4)") (class "Default")
      (node (ref "D602") (pin "16") (pinfunction "C4_16") (pintype "passive"))
      (node (ref "U602") (pin "14") (pinfunction "LED6_14") (pintype "output"))
    )
    (net (code "41") (name "Net-(D602-C5)") (class "Default")
      (node (ref "D602") (pin "15") (pinfunction "C5_15") (pintype "passive"))
      (node (ref "U602") (pin "15") (pinfunction "LED5_15") (pintype "output"))
    )
    (net (code "42") (name "Net-(D602-C6)") (class "Default")
      (node (ref "D602") (pin "14") (pinfunction "C6_14") (pintype "passive"))
      (node (ref "U602") (pin "16") (pinfunction "LED4_16") (pintype "output"))
    )
    (net (code "43") (name "Net-(D602-C7)") (class "Default")
      (node (ref "D602") (pin "13") (pinfunction "C7_13") (pintype "passive"))
      (node (ref "U602") (pin "17") (pinfunction "LED3_17") (pintype "output"))
    )
    (net (code "44") (name "Net-(D602-C8)") (class "Default")
      (node (ref "D602") (pin "12") (pinfunction "C8_12") (pintype "passive"))
      (node (ref "U602") (pin "18") (pinfunction "LED2_18") (pintype "output"))
    )
    (net (code "45") (name "Net-(D602-C9)") (class "Default")
      (node (ref "D602") (pin "11") (pinfunction "C9_11") (pintype "passive"))
      (node (ref "U602") (pin "1") (pinfunction "LED1_1") (pintype "output"))
    )
    (net (code "46") (name "Net-(FB1-2)") (class "Default")
      (node (ref "C3") (pin "1") (pinfunction "1_1") (pintype "passive"))
      (node (ref "FB1") (pin "P$2") (pinfunction "2_P$2") (pintype "passive"))
      (node (ref "J601") (pin "1") (pinfunction "1_1") (pintype "passive"))
    )
    (net (code "47") (name "Net-(IC101-RG1)") (class "Default")
      (node (ref "D102") (pin "A") (pinfunction "A_A") (pintype "passive"))
      (node (ref "IC101") (pin "1") (pinfunction "RG1_1") (pintype "bidirectional"))
      (node (ref "VR101") (pin "CCW") (pinfunction "A_CCW") (pintype "passive"))
      (node (ref "VR101") (pin "WIP") (pinfunction "S_WIP") (pintype "passive"))
    )
    (net (code "48") (name "Net-(R1-1)") (class "Default")
      (node (ref "R1") (pin "P$1") (pinfunction "1_P$1") (pintype "passive"))
      (node (ref "U602") (pin "6") (pinfunction "RHI_6") (pintype "input"))
      (node (ref "U602") (pin "7") (pinfunction "REFOUT_7") (pintype "output"))
    )
    (net (code "49") (name "Net-(R1-2)") (class "Default")
      (node (ref "R1") (pin "P$2") (pinfunction "2_P$2") (pintype "passive"))
      (node (ref "R2") (pin "P$1") (pinfunction "1_P$1") (pintype "passive"))
      (node (ref "U602") (pin "8") (pinfunction "REFADJ_8") (pintype "passive"))
    )
    (net (code "50") (name "Net-(R101-2)") (class "Default")
      (node (ref "J103") (pin "1") (pinfunction "1_1") (pintype "passive"))
      (node (ref "R101") (pin "P$2") (pinfunction "2_P$2") (pintype "passive"))
      (node (ref "R102") (pin "P$2") (pinfunction "2_P$2") (pintype "passive"))
    )
    (net (code "51") (name "Net-(R107-1)") (class "Default")
      (node (ref "R107") (pin "P$1") (pinfunction "1_P$1") (pintype "passive"))
      (node (ref "R108") (pin "P$2") (pinfunction "2_P$2") (pintype "passive"))
      (node (ref "R109") (pin "P$1") (pinfunction "1_P$1") (pintype "passive"))
    )
    (net (code "52") (name "Net-(R110-1)") (class "Default")
      (node (ref "R110") (pin "P$1") (pinfunction "1_P$1") (pintype "passive"))
      (node (ref "VR101") (pin "CW") (pinfunction "E_CW") (pintype "passive"))
    )
    (net (code "53") (name "Net-(R113-1)") (class "Default")
      (node (ref "C119") (pin "1") (pinfunction "1_1") (pintype "passive"))
      (node (ref "R113") (pin "P$1") (pinfunction "1_P$1") (pintype "passive"))
      (node (ref "R114") (pin "P$2") (pinfunction "2_P$2") (pintype "passive"))
      (node (ref "U101") (pin "2") (pinfunction "-IN_2") (pintype "input"))
    )
    (net (code "54") (name "Net-(R114-1)") (class "Default")
      (node (ref "R114") (pin "P$1") (pinfunction "1_P$1") (pintype "passive"))
      (node (ref "VR103") (pin "WIP") (pinfunction "S_WIP") (pintype "passive"))
    )
    (net (code "55") (name "Net-(R601-1)") (class "Default")
      (node (ref "R601") (pin "P$1") (pinfunction "1_P$1") (pintype "passive"))
      (node (ref "R602") (pin "P$1") (pinfunction "1_P$1") (pintype "passive"))
      (node (ref "R603") (pin "P$1") (pinfunction "1_P$1") (pintype "passive"))
      (node (ref "R604") (pin "P$2") (pinfunction "2_P$2") (pintype "passive"))
      (node (ref "R605") (pin "P$1") (pinfunction "1_P$1") (pintype "passive"))
      (node (ref "U603") (pin "2") (pinfunction "-IN_2") (pintype "input"))
    )
    (net (code "56") (name "Net-(R606-2)") (class "Default")
      (node (ref "R606") (pin "P$2") (pinfunction "2_P$2") (pintype "passive"))
      (node (ref "U603") (pin "3") (pinfunction "+IN_3") (pintype "input"))
    )
    (net (code "57") (name "VCC") (class "Default")
      (node (ref "C112") (pin "1") (pinfunction "1_1") (pintype "passive"))
      (node (ref "C121") (pin "P$1") (pinfunction "1_P$1") (pintype "passive"))
      (node (ref "C2") (pin "1") (pinfunction "+_1") (pintype "passive"))
      (node (ref "C601") (pin "P$1") (pinfunction "1_P$1") (pintype "passive"))
      (node (ref "D1") (pin "POS") (pinfunction "+_POS") (pintype "bidirectional"))
      (node (ref "D101") (pin "POS") (pinfunction "+_POS") (pintype "bidirectional"))
      (node (ref "D602") (pin "1") (pinfunction "A_1") (pintype "passive"))
      (node (ref "D602") (pin "10") (pinfunction "A9_10") (pintype "passive"))
      (node (ref "D602") (pin "2") (pinfunction "A1_2") (pintype "passive"))
      (node (ref "D602") (pin "3") (pinfunction "A2_3") (pintype "passive"))
      (node (ref "D602") (pin "4") (pinfunction "A3_4") (pintype "passive"))
      (node (ref "D602") (pin "5") (pinfunction "A4_5") (pintype "passive"))
      (node (ref "D602") (pin "6") (pinfunction "A5_6") (pintype "passive"))
      (node (ref "D602") (pin "7") (pinfunction "A6_7") (pintype "passive"))
      (node (ref "D602") (pin "8") (pinfunction "A7_8") (pintype "passive"))
      (node (ref "D602") (pin "9") (pinfunction "A8_9") (pintype "passive"))
      (node (ref "IC101") (pin "7") (pinfunction "V+_7") (pintype "bidirectional"))
      (node (ref "U101") (pin "7") (pinfunction "P$V+_7") (pintype "bidirectional"))
      (node (ref "U602") (pin "3") (pinfunction "V+_3") (pintype "power_in"))
      (node (ref "U603") (pin "7") (pinfunction "P$V+_7") (pintype "bidirectional"))
    )
    (net (code "58") (name "VNEG") (class "Default")
      (node (ref "C1") (pin "2") (pinfunction "-_2") (pintype "passive"))
      (node (ref "C113") (pin "1") (pinfunction "1_1") (pintype "passive"))
      (node (ref "C122") (pin "P$2") (pinfunction "2_P$2") (pintype "passive"))
      (node (ref "C603") (pin "P$2") (pinfunction "2_P$2") (pintype "passive"))
      (node (ref "D1") (pin "NEG") (pinfunction "-_NEG") (pintype "bidirectional"))
      (node (ref "D101") (pin "NEG") (pinfunction "-_NEG") (pintype "bidirectional"))
      (node (ref "IC101") (pin "4") (pinfunction "V-_4") (pintype "bidirectional"))
      (node (ref "U101") (pin "4") (pinfunction "P$V-_4") (pintype "bidirectional"))
      (node (ref "U603") (pin "4") (pinfunction "P$V-_4") (pintype "bidirectional"))
    )
    (net (code "59") (name "unconnected-(U602-MODE-Pad9)") (class "Default")
      (node (ref "U602") (pin "9") (pinfunction "MODE_9") (pintype "input"))
    )
    (net (code "60") (name "unconnected-(U602-RLO-Pad4)") (class "Default")
      (node (ref "U602") (pin "4") (pinfunction "RLO_4") (pintype "input"))
    )
  )
)
